# TemplateNut.net
KiCad netlist of a schematic drawn in EAGLE
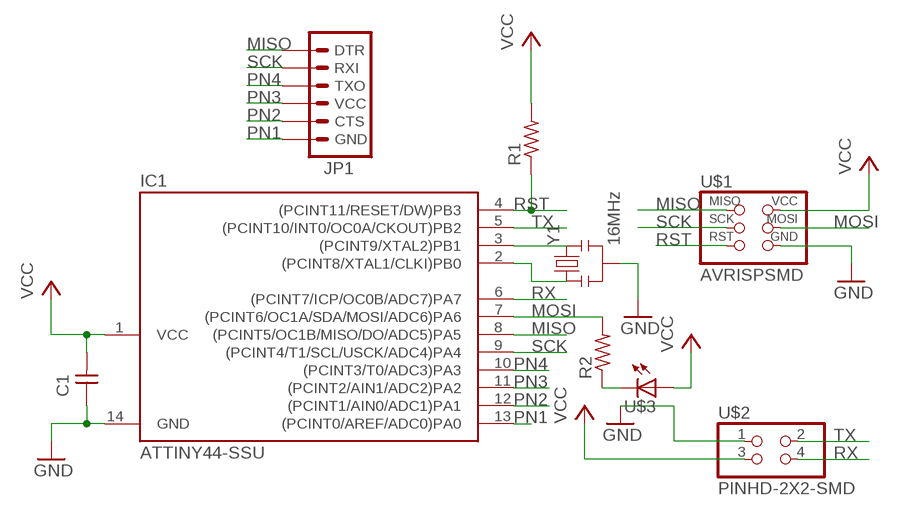
[diagram p0: schematic, sheet 1]

(export (version "E")
  (design (tool "Eeschema 10.0.6"))
  (components
    (comp (ref "C1")
      (value "UNPOLARIZED_CAPACITOR1206")
      (footprint "eagle-import:1206")
      (libsource (lib "eagle-import") (part "UNPOLARIZED_CAPACITOR1206"))
    )
    (comp (ref "IC1")
      (value "ATTINY44-SSU")
      (footprint "eagle-import:SOIC14")
      (libsource (lib "eagle-import") (part "ATTINY44-SSU"))
    )
    (comp (ref "JP1")
      (value "FTDI_CONNECTORSMD")
      (footprint "eagle-import:1X06-SMD")
      (libsource (lib "eagle-import") (part "FTDI_CONNECTORSMD"))
    )
    (comp (ref "R1")
      (value "RESISTOR1206")
      (footprint "eagle-import:1206")
      (libsource (lib "eagle-import") (part "RESISTOR1206"))
    )
    (comp (ref "R2")
      (value "RESISTOR1206")
      (footprint "eagle-import:1206")
      (libsource (lib "eagle-import") (part "RESISTOR1206"))
    )
    (comp (ref "U$1")
      (value "AVRISPSMD")
      (footprint "eagle-import:2X03SMD")
      (libsource (lib "eagle-import") (part "AVRISPSMD"))
    )
    (comp (ref "U$2")
      (value "PINHD-2X2-SMD")
      (footprint "eagle-import:2X02SMD")
      (libsource (lib "eagle-import") (part "PINHD-2X2-SMD"))
    )
    (comp (ref "U$3")
      (value "LED1206")
      (footprint "eagle-import:1206")
      (libsource (lib "eagle-import") (part "LED1206"))
    )
    (comp (ref "Y1")
      (value "16MHz")
      (footprint "eagle-import:RESONATOR-SMD")
      (libsource (lib "eagle-import") (part "RESONATOR16MHZ"))
    )
  )
  (nets
    (net (code "1") (name "/MISO") (class "Default")
      (node (ref "IC1") (pin "8") (pinfunction "(PCINT5/OC1B/MISO/DO/ADC5)PA5_8") (pintype "bidirectional"))
      (node (ref "JP1") (pin "1") (pinfunction "DTR_1") (pintype "passive"))
      (node (ref "U$1") (pin "1") (pinfunction "MISO_1") (pintype "passive"))
    )
    (net (code "2") (name "/MOSI") (class "Default")
      (node (ref "IC1") (pin "7") (pinfunction "(PCINT6/OC1A/SDA/MOSI/ADC6)PA6_7") (pintype "bidirectional"))
      (node (ref "R2") (pin "2") (pinfunction "2_2") (pintype "passive"))
      (node (ref "U$1") (pin "4") (pinfunction "MOSI_4") (pintype "passive"))
    )
    (net (code "3") (name "/PN1") (class "Default")
      (node (ref "IC1") (pin "13") (pinfunction "(PCINT0/AREF/ADC0)PA0_13") (pintype "bidirectional"))
      (node (ref "JP1") (pin "6") (pinfunction "GND_6") (pintype "passive"))
    )
    (net (code "4") (name "/PN2") (class "Default")
      (node (ref "IC1") (pin "12") (pinfunction "(PCINT1/AIN0/ADC1)PA1_12") (pintype "bidirectional"))
      (node (ref "JP1") (pin "5") (pinfunction "CTS_5") (pintype "passive"))
    )
    (net (code "5") (name "/PN3") (class "Default")
      (node (ref "IC1") (pin "11") (pinfunction "(PCINT2/AIN1/ADC2)PA2_11") (pintype "bidirectional"))
      (node (ref "JP1") (pin "4") (pinfunction "VCC_4") (pintype "passive"))
    )
    (net (code "6") (name "/PN4") (class "Default")
      (node (ref "IC1") (pin "10") (pinfunction "(PCINT3/T0/ADC3)PA3_10") (pintype "bidirectional"))
      (node (ref "JP1") (pin "3") (pinfunction "TXO_3") (pintype "passive"))
    )
    (net (code "7") (name "/RST") (class "Default")
      (node (ref "IC1") (pin "4") (pinfunction "(PCINT11/RESET/DW)PB3_4") (pintype "bidirectional"))
      (node (ref "R1") (pin "1") (pinfunction "1_1") (pintype "passive"))
      (node (ref "U$1") (pin "5") (pinfunction "RST_5") (pintype "passive"))
    )
    (net (code "8") (name "/RX") (class "Default")
      (node (ref "IC1") (pin "6") (pinfunction "(PCINT7/ICP/OC0B/ADC7)PA7_6") (pintype "bidirectional"))
      (node (ref "U$2") (pin "4") (pinfunction "4_4") (pintype "passive"))
    )
    (net (code "9") (name "/SCK") (class "Default")
      (node (ref "IC1") (pin "9") (pinfunction "(PCINT4/T1/SCL/USCK/ADC4)PA4_9") (pintype "bidirectional"))
      (node (ref "JP1") (pin "2") (pinfunction "RXI_2") (pintype "passive"))
      (node (ref "U$1") (pin "3") (pinfunction "SCK_3") (pintype "passive"))
    )
    (net (code "10") (name "/TX") (class "Default")
      (node (ref "IC1") (pin "5") (pinfunction "(PCINT10/INT0/OC0A/CKOUT)PB2_5") (pintype "bidirectional"))
      (node (ref "U$2") (pin "2") (pinfunction "2_2") (pintype "passive"))
    )
    (net (code "11") (name "GND") (class "Default")
      (node (ref "C1") (pin "1") (pinfunction "1_1") (pintype "passive"))
      (node (ref "IC1") (pin "14") (pinfunction "GND_14") (pintype "power_in"))
      (node (ref "U$1") (pin "6") (pinfunction "GND_6") (pintype "passive"))
      (node (ref "U$2") (pin "1") (pinfunction "1_1") (pintype "passive"))
      (node (ref "Y1") (pin "2") (pinfunction "2_2") (pintype "passive"))
    )
    (net (code "12") (name "Net-(IC1-(PCINT8{slash}XTAL1{slash}CLKI)PB0)") (class "Default")
      (node (ref "IC1") (pin "2") (pinfunction "(PCINT8/XTAL1/CLKI)PB0_2") (pintype "bidirectional"))
      (node (ref "Y1") (pin "1") (pinfunction "1_1") (pintype "passive"))
    )
    (net (code "13") (name "Net-(IC1-(PCINT9{slash}XTAL2)PB1)") (class "Default")
      (node (ref "IC1") (pin "3") (pinfunction "(PCINT9/XTAL2)PB1_3") (pintype "bidirectional"))
      (node (ref "Y1") (pin "3") (pinfunction "3_3") (pintype "passive"))
    )
    (net (code "14") (name "Net-(U$3-C)") (class "Default")
      (node (ref "R2") (pin "1") (pinfunction "1_1") (pintype "passive"))
      (node (ref "U$3") (pin "2") (pinfunction "C_2") (pintype "passive"))
    )
    (net (code "15") (name "VCC") (class "Default")
      (node (ref "C1") (pin "2") (pinfunction "2_2") (pintype "passive"))
      (node (ref "IC1") (pin "1") (pinfunction "VCC_1") (pintype "power_in"))
      (node (ref "R1") (pin "2") (pinfunction "2_2") (pintype "passive"))
      (node (ref "U$1") (pin "2") (pinfunction "VCC_2") (pintype "passive"))
      (node (ref "U$2") (pin "3") (pinfunction "3_3") (pintype "passive"))
      (node (ref "U$3") (pin "1") (pinfunction "A_1") (pintype "passive"))
    )
  )
)
